# one_wire_master.net
KiCad netlist of a schematic drawn in EAGLE
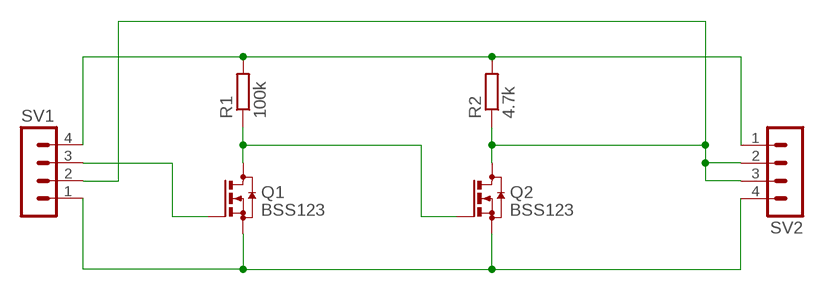
[diagram p0: schematic, sheet 1]

(export (version "E")
  (design (tool "Eeschema 10.0.6"))
  (components
    (comp (ref "Q1")
      (value "BSS123")
      (footprint "eagle-import:SOT23")
      (libsource (lib "eagle-import") (part "BSS123"))
    )
    (comp (ref "Q2")
      (value "BSS123")
      (footprint "eagle-import:SOT23")
      (libsource (lib "eagle-import") (part "BSS123"))
    )
    (comp (ref "R1")
      (value "100k")
      (footprint "eagle-import:M0805")
      (libsource (lib "eagle-import") (part "R-EU_M0805"))
    )
    (comp (ref "R2")
      (value "4.7k")
      (footprint "eagle-import:M0805")
      (libsource (lib "eagle-import") (part "R-EU_M0805"))
    )
    (comp (ref "SV1")
      (value "MA04-1")
      (footprint "eagle-import:MA04-1")
      (libsource (lib "eagle-import") (part "MA04-1"))
    )
    (comp (ref "SV2")
      (value "MA04-1")
      (footprint "eagle-import:MA04-1")
      (libsource (lib "eagle-import") (part "MA04-1"))
    )
  )
  (nets
    (net (code "1") (name "Net-(Q1-D)") (class "Default")
      (node (ref "Q1") (pin "3") (pinfunction "D_3") (pintype "passive"))
      (node (ref "Q2") (pin "1") (pinfunction "G_1") (pintype "passive"))
      (node (ref "R1") (pin "1") (pinfunction "1_1") (pintype "passive"))
    )
    (net (code "2") (name "Net-(Q1-G)") (class "Default")
      (node (ref "Q1") (pin "1") (pinfunction "G_1") (pintype "passive"))
      (node (ref "SV1") (pin "3") (pinfunction "3_3") (pintype "passive"))
    )
    (net (code "3") (name "Net-(Q1-S)") (class "Default")
      (node (ref "Q1") (pin "2") (pinfunction "S_2") (pintype "passive"))
      (node (ref "Q2") (pin "2") (pinfunction "S_2") (pintype "passive"))
      (node (ref "SV1") (pin "1") (pinfunction "1_1") (pintype "passive"))
      (node (ref "SV2") (pin "4") (pinfunction "4_4") (pintype "passive"))
    )
    (net (code "4") (name "Net-(Q2-D)") (class "Default")
      (node (ref "Q2") (pin "3") (pinfunction "D_3") (pintype "passive"))
      (node (ref "R2") (pin "1") (pinfunction "1_1") (pintype "passive"))
      (node (ref "SV1") (pin "2") (pinfunction "2_2") (pintype "passive"))
      (node (ref "SV2") (pin "2") (pinfunction "2_2") (pintype "passive"))
      (node (ref "SV2") (pin "3") (pinfunction "3_3") (pintype "passive"))
    )
    (net (code "5") (name "Net-(R1-Pad2)") (class "Default")
      (node (ref "R1") (pin "2") (pinfunction "2_2") (pintype "passive"))
      (node (ref "R2") (pin "2") (pinfunction "2_2") (pintype "passive"))
      (node (ref "SV1") (pin "4") (pinfunction "4_4") (pintype "passive"))
      (node (ref "SV2") (pin "1") (pinfunction "1_1") (pintype "passive"))
    )
  )
)
